# ECU_Freio_2024_Equipe_Imperador.net
KiCad netlist of a schematic drawn in Altium Designer
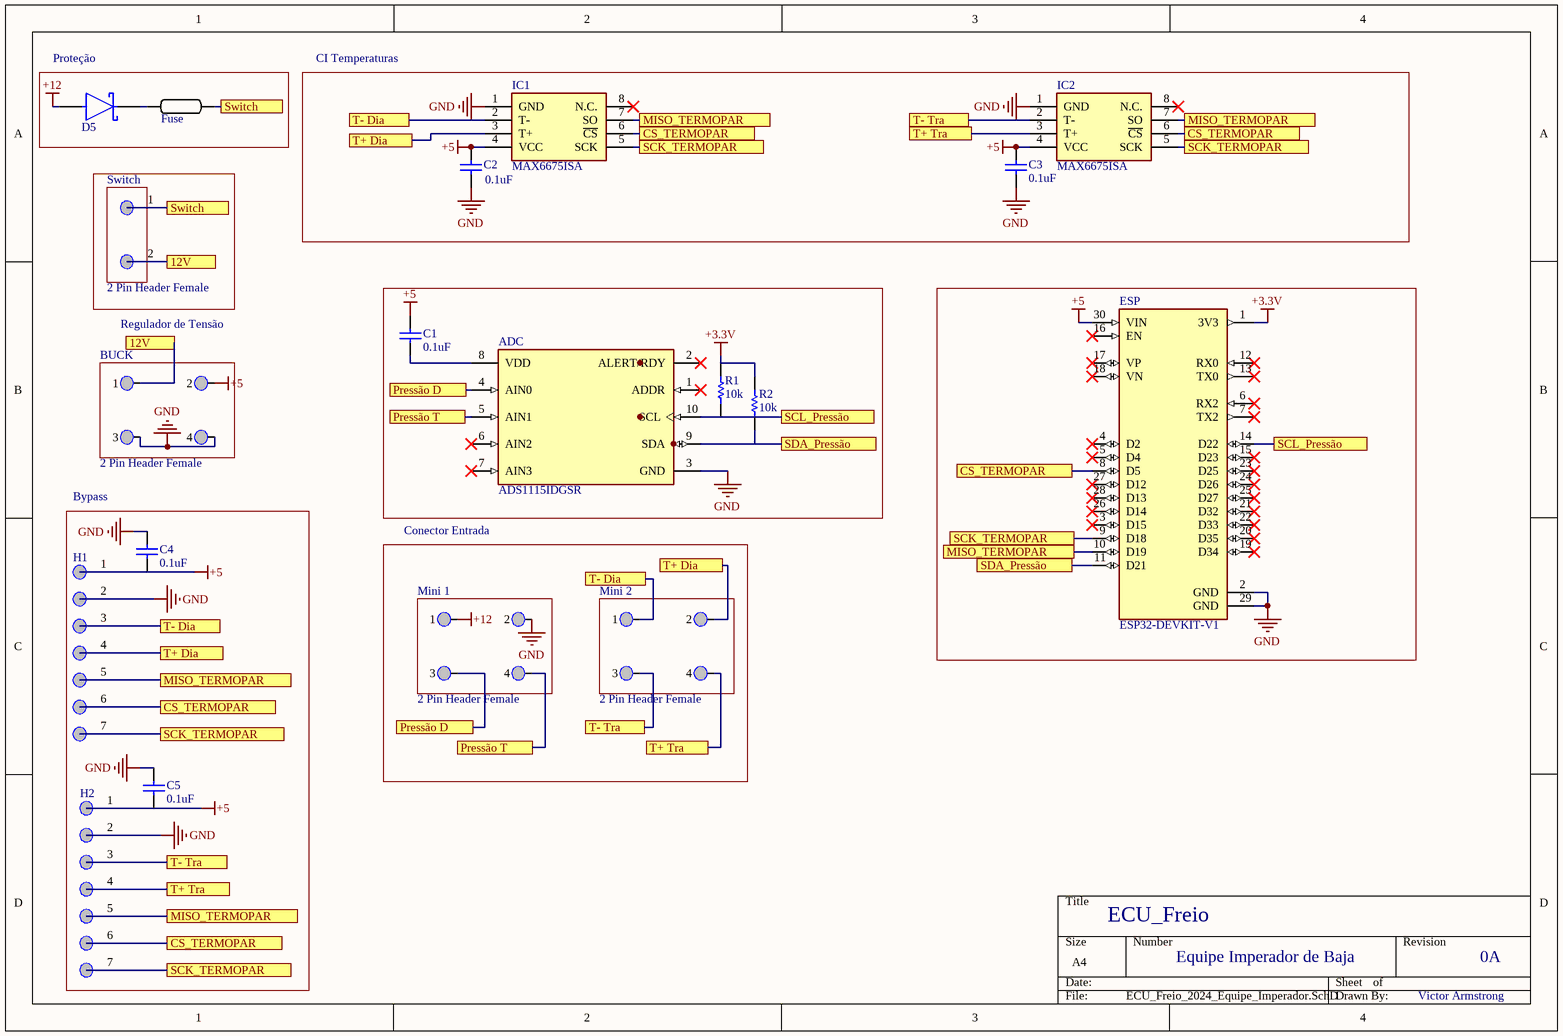
[diagram p0: ECU_Freio_2024_Equipe_Imperador.SchDoc]

(export (version "E")
  (design (tool "Eeschema 10.0.6"))
  (components
    (comp (ref "ADC")
      (value "ADS1115IDGSR")
      (footprint "FP-DGS0010A-IPC_B")
      (description "IC ADC 16BIT SIGMA-DELTA 10VSSOP")
      (libsource (lib "Altium Content Vault") (part "1442cd67780685bba1a77ae27c88037"))
    )
    (comp (ref "BUCK")
      (value "2 Pin Header Female")
      (footprint "CONECTOR MINIFIT 2X2")
      (libsource (lib "Conector MiniFit 2x2") (part "2 Pin Header Female"))
    )
    (comp (ref "C1")
      (value "0.1uF")
      (footprint "CAPC2013X145X50ML20T25")
      (fields (field (name "PART NUMBER") "C0805C225K9PACTU") (field (name "MANUFACTURER") "Kemet"))
      (libsource (lib "Altium Content Vault") (part "CAP"))
    )
    (comp (ref "C2")
      (value "0.1uF")
      (footprint "CAPC2013X145X50ML20T25")
      (fields (field (name "PART NUMBER") "C0805C225K9PACTU") (field (name "MANUFACTURER") "Kemet"))
      (libsource (lib "Altium Content Vault") (part "CAP"))
    )
    (comp (ref "C3")
      (value "0.1uF")
      (footprint "CAPC2013X145X50ML20T25")
      (fields (field (name "PART NUMBER") "C0805C225K9PACTU") (field (name "MANUFACTURER") "Kemet"))
      (libsource (lib "Altium Content Vault") (part "CAP"))
    )
    (comp (ref "C4")
      (value "0.1uF")
      (footprint "CAPC2013X145X50ML20T25")
      (fields (field (name "PART NUMBER") "C0805C225K9PACTU") (field (name "MANUFACTURER") "Kemet"))
      (libsource (lib "Altium Content Vault") (part "CAP"))
    )
    (comp (ref "C5")
      (value "0.1uF")
      (footprint "CAPC2013X145X50ML20T25")
      (fields (field (name "PART NUMBER") "C0805C225K9PACTU") (field (name "MANUFACTURER") "Kemet"))
      (libsource (lib "Altium Content Vault") (part "CAP"))
    )
    (comp (ref "D5")
      (value "BAT54JFILM")
      (footprint "FP-SOD323-MFG")
      (description "DIODE SCHOTTKY 40V 300MA SOD323")
      (fields
        (field (name "OCTOPART") "https://octopart.com/bat54jfilm-stmicroelectronics-326073")
        (field (name "MANUFACTURER") "STMicroelectronics")
      )
      (libsource (lib "Altium Content Vault") (part "1d6ec82d83fb6aee721767c19dac4b9"))
    )
    (comp (ref "ESP")
      (value "ESP32-DEVKIT-V1")
      (footprint "MODULE_ESP32_DEVKIT_V1")
      (fields (field (name "MF") "Do it"))
      (libsource (lib "ESP32-DEVKIT-V1") (part "ESP32-DEVKIT-V1"))
    )
    (comp (ref "Fuse")
      (value "Fuse Holder 5x20mm")
      (footprint "Fuse Holder 5x20mm")
      (libsource (lib "Fuse Holder 5x20mm") (part "Fuse Holder 5x20mm"))
    )
    (comp (ref "H1")
      (value "CONECTOR JST XH 6 PIN_1")
      (footprint "7 Furos")
      (libsource (lib "7 Furos") (part "CONECTOR JST XH 6 PIN_1"))
    )
    (comp (ref "H2")
      (value "CONECTOR JST XH 6 PIN_1")
      (footprint "7 Furos")
      (libsource (lib "7 Furos") (part "CONECTOR JST XH 6 PIN_1"))
    )
    (comp (ref "IC1")
      (value "MAX6675ISA")
      (footprint "SamacSys:SOIC127P600X175-8N")
      (description "Integrated Circuit")
      (libsource (lib "SamacSys") (part "MAX6675ISA"))
    )
    (comp (ref "IC2")
      (value "MAX6675ISA")
      (footprint "SamacSys:SOIC127P600X175-8N")
      (description "Integrated Circuit")
      (libsource (lib "SamacSys") (part "MAX6675ISA"))
    )
    (comp (ref "Mini 1")
      (value "2 Pin Header Female")
      (footprint "CONECTOR MINIFIT 2X2")
      (libsource (lib "Conector MiniFit 2x2") (part "2 Pin Header Female"))
    )
    (comp (ref "Mini 2")
      (value "2 Pin Header Female")
      (footprint "CONECTOR MINIFIT 2X2")
      (libsource (lib "Conector MiniFit 2x2") (part "2 Pin Header Female"))
    )
    (comp (ref "R1")
      (value "10k")
      (footprint "RESC2013X60X35ML10T20")
      (description "Chip Resistor, 1 KOhm, +/- 1%, 125 mW, -55 to 155 degC, 0805 (2012 Metric), RoHS, Tape and Reel")
      (fields (field (name "TOLERANCE") "1%") (field (name "MANUFACTURER") "Yageo"))
      (libsource (lib "Altium Content Vault") (part "RES-2"))
    )
    (comp (ref "R2")
      (value "10k")
      (footprint "RESC2013X60X35ML10T20")
      (description "Chip Resistor, 1 KOhm, +/- 1%, 125 mW, -55 to 155 degC, 0805 (2012 Metric), RoHS, Tape and Reel")
      (fields (field (name "TOLERANCE") "1%") (field (name "MANUFACTURER") "Yageo"))
      (libsource (lib "Altium Content Vault") (part "RES-2"))
    )
    (comp (ref "Switch")
      (value "2 Pin Header Female")
      (footprint "2 Pins Header Female - duplicate")
      (libsource (lib "2 Pin Header Female") (part "2 Pin Header Female"))
    )
  )
  (nets
    (net (code "1") (name "+3.3V") (class "Default")
      (node (ref "ESP") (pin "1") (pinfunction "3V3_1") (pintype "output"))
      (node (ref "R1") (pin "1") (pinfunction "1_1") (pintype "passive"))
      (node (ref "R2") (pin "1") (pinfunction "1_1") (pintype "passive"))
    )
    (net (code "2") (name "+5") (class "Default")
      (node (ref "BUCK") (pin "2") (pinfunction "2_2") (pintype "passive"))
      (node (ref "C1") (pin "1") (pinfunction "1_1") (pintype "passive"))
      (node (ref "C2") (pin "1") (pinfunction "1_1") (pintype "passive"))
      (node (ref "C3") (pin "1") (pinfunction "1_1") (pintype "passive"))
      (node (ref "C4") (pin "1") (pinfunction "1_1") (pintype "passive"))
      (node (ref "C5") (pin "1") (pinfunction "1_1") (pintype "passive"))
      (node (ref "ESP") (pin "30") (pinfunction "VIN_30") (pintype "input"))
      (node (ref "H1") (pin "1") (pinfunction "1_1") (pintype "passive"))
      (node (ref "H2") (pin "1") (pinfunction "1_1") (pintype "passive"))
      (node (ref "IC1") (pin "4") (pinfunction "VCC_4") (pintype "passive"))
      (node (ref "IC2") (pin "4") (pinfunction "VCC_4") (pintype "passive"))
    )
    (net (code "3") (name "+12") (class "Default")
      (node (ref "D5") (pin "2") (pinfunction "A_2") (pintype "passive"))
      (node (ref "Mini 1") (pin "1") (pinfunction "1_1") (pintype "passive"))
    )
    (net (code "4") (name "/12V") (class "Default")
      (node (ref "BUCK") (pin "1") (pinfunction "1_1") (pintype "passive"))
      (node (ref "Switch") (pin "2") (pinfunction "2_2") (pintype "passive"))
    )
    (net (code "5") (name "/CS_TERMOPAR") (class "Default")
      (node (ref "ESP") (pin "8") (pinfunction "D5_8") (pintype "bidirectional"))
      (node (ref "H1") (pin "6") (pinfunction "6_6") (pintype "passive"))
      (node (ref "H2") (pin "6") (pinfunction "6_6") (pintype "passive"))
      (node (ref "IC1") (pin "6") (pinfunction "~{CS}_6") (pintype "passive"))
      (node (ref "IC2") (pin "6") (pinfunction "~{CS}_6") (pintype "passive"))
    )
    (net (code "6") (name "/MISO_TERMOPAR") (class "Default")
      (node (ref "ESP") (pin "10") (pinfunction "D19_10") (pintype "bidirectional"))
      (node (ref "H1") (pin "5") (pinfunction "5_5") (pintype "passive"))
      (node (ref "H2") (pin "5") (pinfunction "5_5") (pintype "passive"))
      (node (ref "IC1") (pin "7") (pinfunction "SO_7") (pintype "passive"))
      (node (ref "IC2") (pin "7") (pinfunction "SO_7") (pintype "passive"))
    )
    (net (code "7") (name "/Pressão D") (class "Default")
      (node (ref "ADC") (pin "4") (pinfunction "AIN0_4") (pintype "input"))
      (node (ref "Mini 1") (pin "3") (pinfunction "3_3") (pintype "passive"))
    )
    (net (code "8") (name "/Pressão T") (class "Default")
      (node (ref "ADC") (pin "5") (pinfunction "AIN1_5") (pintype "input"))
      (node (ref "Mini 1") (pin "4") (pinfunction "4_4") (pintype "passive"))
    )
    (net (code "9") (name "/SCK_TERMOPAR") (class "Default")
      (node (ref "ESP") (pin "9") (pinfunction "D18_9") (pintype "bidirectional"))
      (node (ref "H1") (pin "7") (pinfunction "7_7") (pintype "passive"))
      (node (ref "H2") (pin "7") (pinfunction "7_7") (pintype "passive"))
      (node (ref "IC1") (pin "5") (pinfunction "SCK_5") (pintype "passive"))
      (node (ref "IC2") (pin "5") (pinfunction "SCK_5") (pintype "passive"))
    )
    (net (code "10") (name "/SCL_Pressão") (class "Default")
      (node (ref "ADC") (pin "10") (pinfunction "SCL_10") (pintype "input"))
      (node (ref "ESP") (pin "14") (pinfunction "D22_14") (pintype "bidirectional"))
      (node (ref "R1") (pin "2") (pinfunction "2_2") (pintype "passive"))
    )
    (net (code "11") (name "/SDA_Pressão") (class "Default")
      (node (ref "ADC") (pin "9") (pinfunction "SDA_9") (pintype "bidirectional"))
      (node (ref "ESP") (pin "11") (pinfunction "D21_11") (pintype "bidirectional"))
      (node (ref "R2") (pin "2") (pinfunction "2_2") (pintype "passive"))
    )
    (net (code "12") (name "/Switch") (class "Default")
      (node (ref "Fuse") (pin "1") (pinfunction "1_1") (pintype "passive"))
      (node (ref "Switch") (pin "1") (pinfunction "1_1") (pintype "passive"))
    )
    (net (code "13") (name "/T+ Dia") (class "Default")
      (node (ref "H1") (pin "4") (pinfunction "4_4") (pintype "passive"))
      (node (ref "IC1") (pin "3") (pinfunction "T+_3") (pintype "passive"))
      (node (ref "Mini 2") (pin "2") (pinfunction "2_2") (pintype "passive"))
    )
    (net (code "14") (name "/T+ Tra") (class "Default")
      (node (ref "H2") (pin "4") (pinfunction "4_4") (pintype "passive"))
      (node (ref "IC2") (pin "3") (pinfunction "T+_3") (pintype "passive"))
      (node (ref "Mini 2") (pin "4") (pinfunction "4_4") (pintype "passive"))
    )
    (net (code "15") (name "/T- Dia") (class "Default")
      (node (ref "H1") (pin "3") (pinfunction "3_3") (pintype "passive"))
      (node (ref "IC1") (pin "2") (pinfunction "T-_2") (pintype "passive"))
      (node (ref "Mini 2") (pin "1") (pinfunction "1_1") (pintype "passive"))
    )
    (net (code "16") (name "/T- Tra") (class "Default")
      (node (ref "H2") (pin "3") (pinfunction "3_3") (pintype "passive"))
      (node (ref "IC2") (pin "2") (pinfunction "T-_2") (pintype "passive"))
      (node (ref "Mini 2") (pin "3") (pinfunction "3_3") (pintype "passive"))
    )
    (net (code "17") (name "GND") (class "Default")
      (node (ref "ADC") (pin "3") (pinfunction "GND_3") (pintype "power_in"))
      (node (ref "BUCK") (pin "3") (pinfunction "3_3") (pintype "passive"))
      (node (ref "BUCK") (pin "4") (pinfunction "4_4") (pintype "passive"))
      (node (ref "C2") (pin "2") (pinfunction "2_2") (pintype "passive"))
      (node (ref "C3") (pin "2") (pinfunction "2_2") (pintype "passive"))
      (node (ref "C4") (pin "2") (pinfunction "2_2") (pintype "passive"))
      (node (ref "C5") (pin "2") (pinfunction "2_2") (pintype "passive"))
      (node (ref "ESP") (pin "2") (pinfunction "GND_2") (pintype "power_in"))
      (node (ref "ESP") (pin "29") (pinfunction "GND_29") (pintype "power_in"))
      (node (ref "H1") (pin "2") (pinfunction "2_2") (pintype "passive"))
      (node (ref "H2") (pin "2") (pinfunction "2_2") (pintype "passive"))
      (node (ref "IC1") (pin "1") (pinfunction "GND_1") (pintype "passive"))
      (node (ref "IC2") (pin "1") (pinfunction "GND_1") (pintype "passive"))
      (node (ref "Mini 1") (pin "2") (pinfunction "2_2") (pintype "passive"))
    )
    (net (code "18") (name "Net-(ADC-VDD)") (class "Default")
      (node (ref "ADC") (pin "8") (pinfunction "VDD_8") (pintype "power_in"))
      (node (ref "C1") (pin "2") (pinfunction "2_2") (pintype "passive"))
    )
    (net (code "19") (name "Net-(D5-C)") (class "Default")
      (node (ref "D5") (pin "1") (pinfunction "C_1") (pintype "passive"))
      (node (ref "Fuse") (pin "2") (pinfunction "2_2") (pintype "passive"))
    )
    (net (code "20") (name "unconnected-(ADC-ADDR-Pad1)") (class "Default")
      (node (ref "ADC") (pin "1") (pinfunction "ADDR_1") (pintype "input+no_connect"))
    )
    (net (code "21") (name "unconnected-(ADC-AIN2-Pad6)") (class "Default")
      (node (ref "ADC") (pin "6") (pinfunction "AIN2_6") (pintype "input+no_connect"))
    )
    (net (code "22") (name "unconnected-(ADC-AIN3-Pad7)") (class "Default")
      (node (ref "ADC") (pin "7") (pinfunction "AIN3_7") (pintype "input+no_connect"))
    )
    (net (code "23") (name "unconnected-(ADC-ALERT{slash}RDY-Pad2)") (class "Default")
      (node (ref "ADC") (pin "2") (pinfunction "ALERT/RDY_2") (pintype "open_collector+no_connect"))
    )
    (net (code "24") (name "unconnected-(ESP-D2-Pad4)") (class "Default")
      (node (ref "ESP") (pin "4") (pinfunction "D2_4") (pintype "bidirectional+no_connect"))
    )
    (net (code "25") (name "unconnected-(ESP-D4-Pad5)") (class "Default")
      (node (ref "ESP") (pin "5") (pinfunction "D4_5") (pintype "bidirectional+no_connect"))
    )
    (net (code "26") (name "unconnected-(ESP-D12-Pad27)") (class "Default")
      (node (ref "ESP") (pin "27") (pinfunction "D12_27") (pintype "bidirectional+no_connect"))
    )
    (net (code "27") (name "unconnected-(ESP-D13-Pad28)") (class "Default")
      (node (ref "ESP") (pin "28") (pinfunction "D13_28") (pintype "bidirectional+no_connect"))
    )
    (net (code "28") (name "unconnected-(ESP-D14-Pad26)") (class "Default")
      (node (ref "ESP") (pin "26") (pinfunction "D14_26") (pintype "bidirectional+no_connect"))
    )
    (net (code "29") (name "unconnected-(ESP-D15-Pad3)") (class "Default")
      (node (ref "ESP") (pin "3") (pinfunction "D15_3") (pintype "bidirectional+no_connect"))
    )
    (net (code "30") (name "unconnected-(ESP-D23-Pad15)") (class "Default")
      (node (ref "ESP") (pin "15") (pinfunction "D23_15") (pintype "bidirectional+no_connect"))
    )
    (net (code "31") (name "unconnected-(ESP-D25-Pad23)") (class "Default")
      (node (ref "ESP") (pin "23") (pinfunction "D25_23") (pintype "bidirectional+no_connect"))
    )
    (net (code "32") (name "unconnected-(ESP-D26-Pad24)") (class "Default")
      (node (ref "ESP") (pin "24") (pinfunction "D26_24") (pintype "bidirectional+no_connect"))
    )
    (net (code "33") (name "unconnected-(ESP-D27-Pad25)") (class "Default")
      (node (ref "ESP") (pin "25") (pinfunction "D27_25") (pintype "bidirectional+no_connect"))
    )
    (net (code "34") (name "unconnected-(ESP-D32-Pad21)") (class "Default")
      (node (ref "ESP") (pin "21") (pinfunction "D32_21") (pintype "bidirectional+no_connect"))
    )
    (net (code "35") (name "unconnected-(ESP-D33-Pad22)") (class "Default")
      (node (ref "ESP") (pin "22") (pinfunction "D33_22") (pintype "bidirectional+no_connect"))
    )
    (net (code "36") (name "unconnected-(ESP-D34-Pad19)") (class "Default")
      (node (ref "ESP") (pin "19") (pinfunction "D34_19") (pintype "bidirectional+no_connect"))
    )
    (net (code "37") (name "unconnected-(ESP-D35-Pad20)") (class "Default")
      (node (ref "ESP") (pin "20") (pinfunction "D35_20") (pintype "bidirectional+no_connect"))
    )
    (net (code "38") (name "unconnected-(ESP-EN-Pad16)") (class "Default")
      (node (ref "ESP") (pin "16") (pinfunction "EN_16") (pintype "input+no_connect"))
    )
    (net (code "39") (name "unconnected-(ESP-RX0-Pad12)") (class "Default")
      (node (ref "ESP") (pin "12") (pinfunction "RX0_12") (pintype "input+no_connect"))
    )
    (net (code "40") (name "unconnected-(ESP-RX2-Pad6)") (class "Default")
      (node (ref "ESP") (pin "6") (pinfunction "RX2_6") (pintype "input+no_connect"))
    )
    (net (code "41") (name "unconnected-(ESP-TX0-Pad13)") (class "Default")
      (node (ref "ESP") (pin "13") (pinfunction "TX0_13") (pintype "output+no_connect"))
    )
    (net (code "42") (name "unconnected-(ESP-TX2-Pad7)") (class "Default")
      (node (ref "ESP") (pin "7") (pinfunction "TX2_7") (pintype "output+no_connect"))
    )
    (net (code "43") (name "unconnected-(ESP-VN-Pad18)") (class "Default")
      (node (ref "ESP") (pin "18") (pinfunction "VN_18") (pintype "bidirectional+no_connect"))
    )
    (net (code "44") (name "unconnected-(ESP-VP-Pad17)") (class "Default")
      (node (ref "ESP") (pin "17") (pinfunction "VP_17") (pintype "bidirectional+no_connect"))
    )
    (net (code "45") (name "unconnected-(IC1-N.C.-Pad8)") (class "Default")
      (node (ref "IC1") (pin "8") (pinfunction "N.C._8") (pintype "passive+no_connect"))
    )
    (net (code "46") (name "unconnected-(IC2-N.C.-Pad8)") (class "Default")
      (node (ref "IC2") (pin "8") (pinfunction "N.C._8") (pintype "passive+no_connect"))
    )
  )
)
